# carcomputer.net
KiCad netlist of a schematic drawn in EAGLE
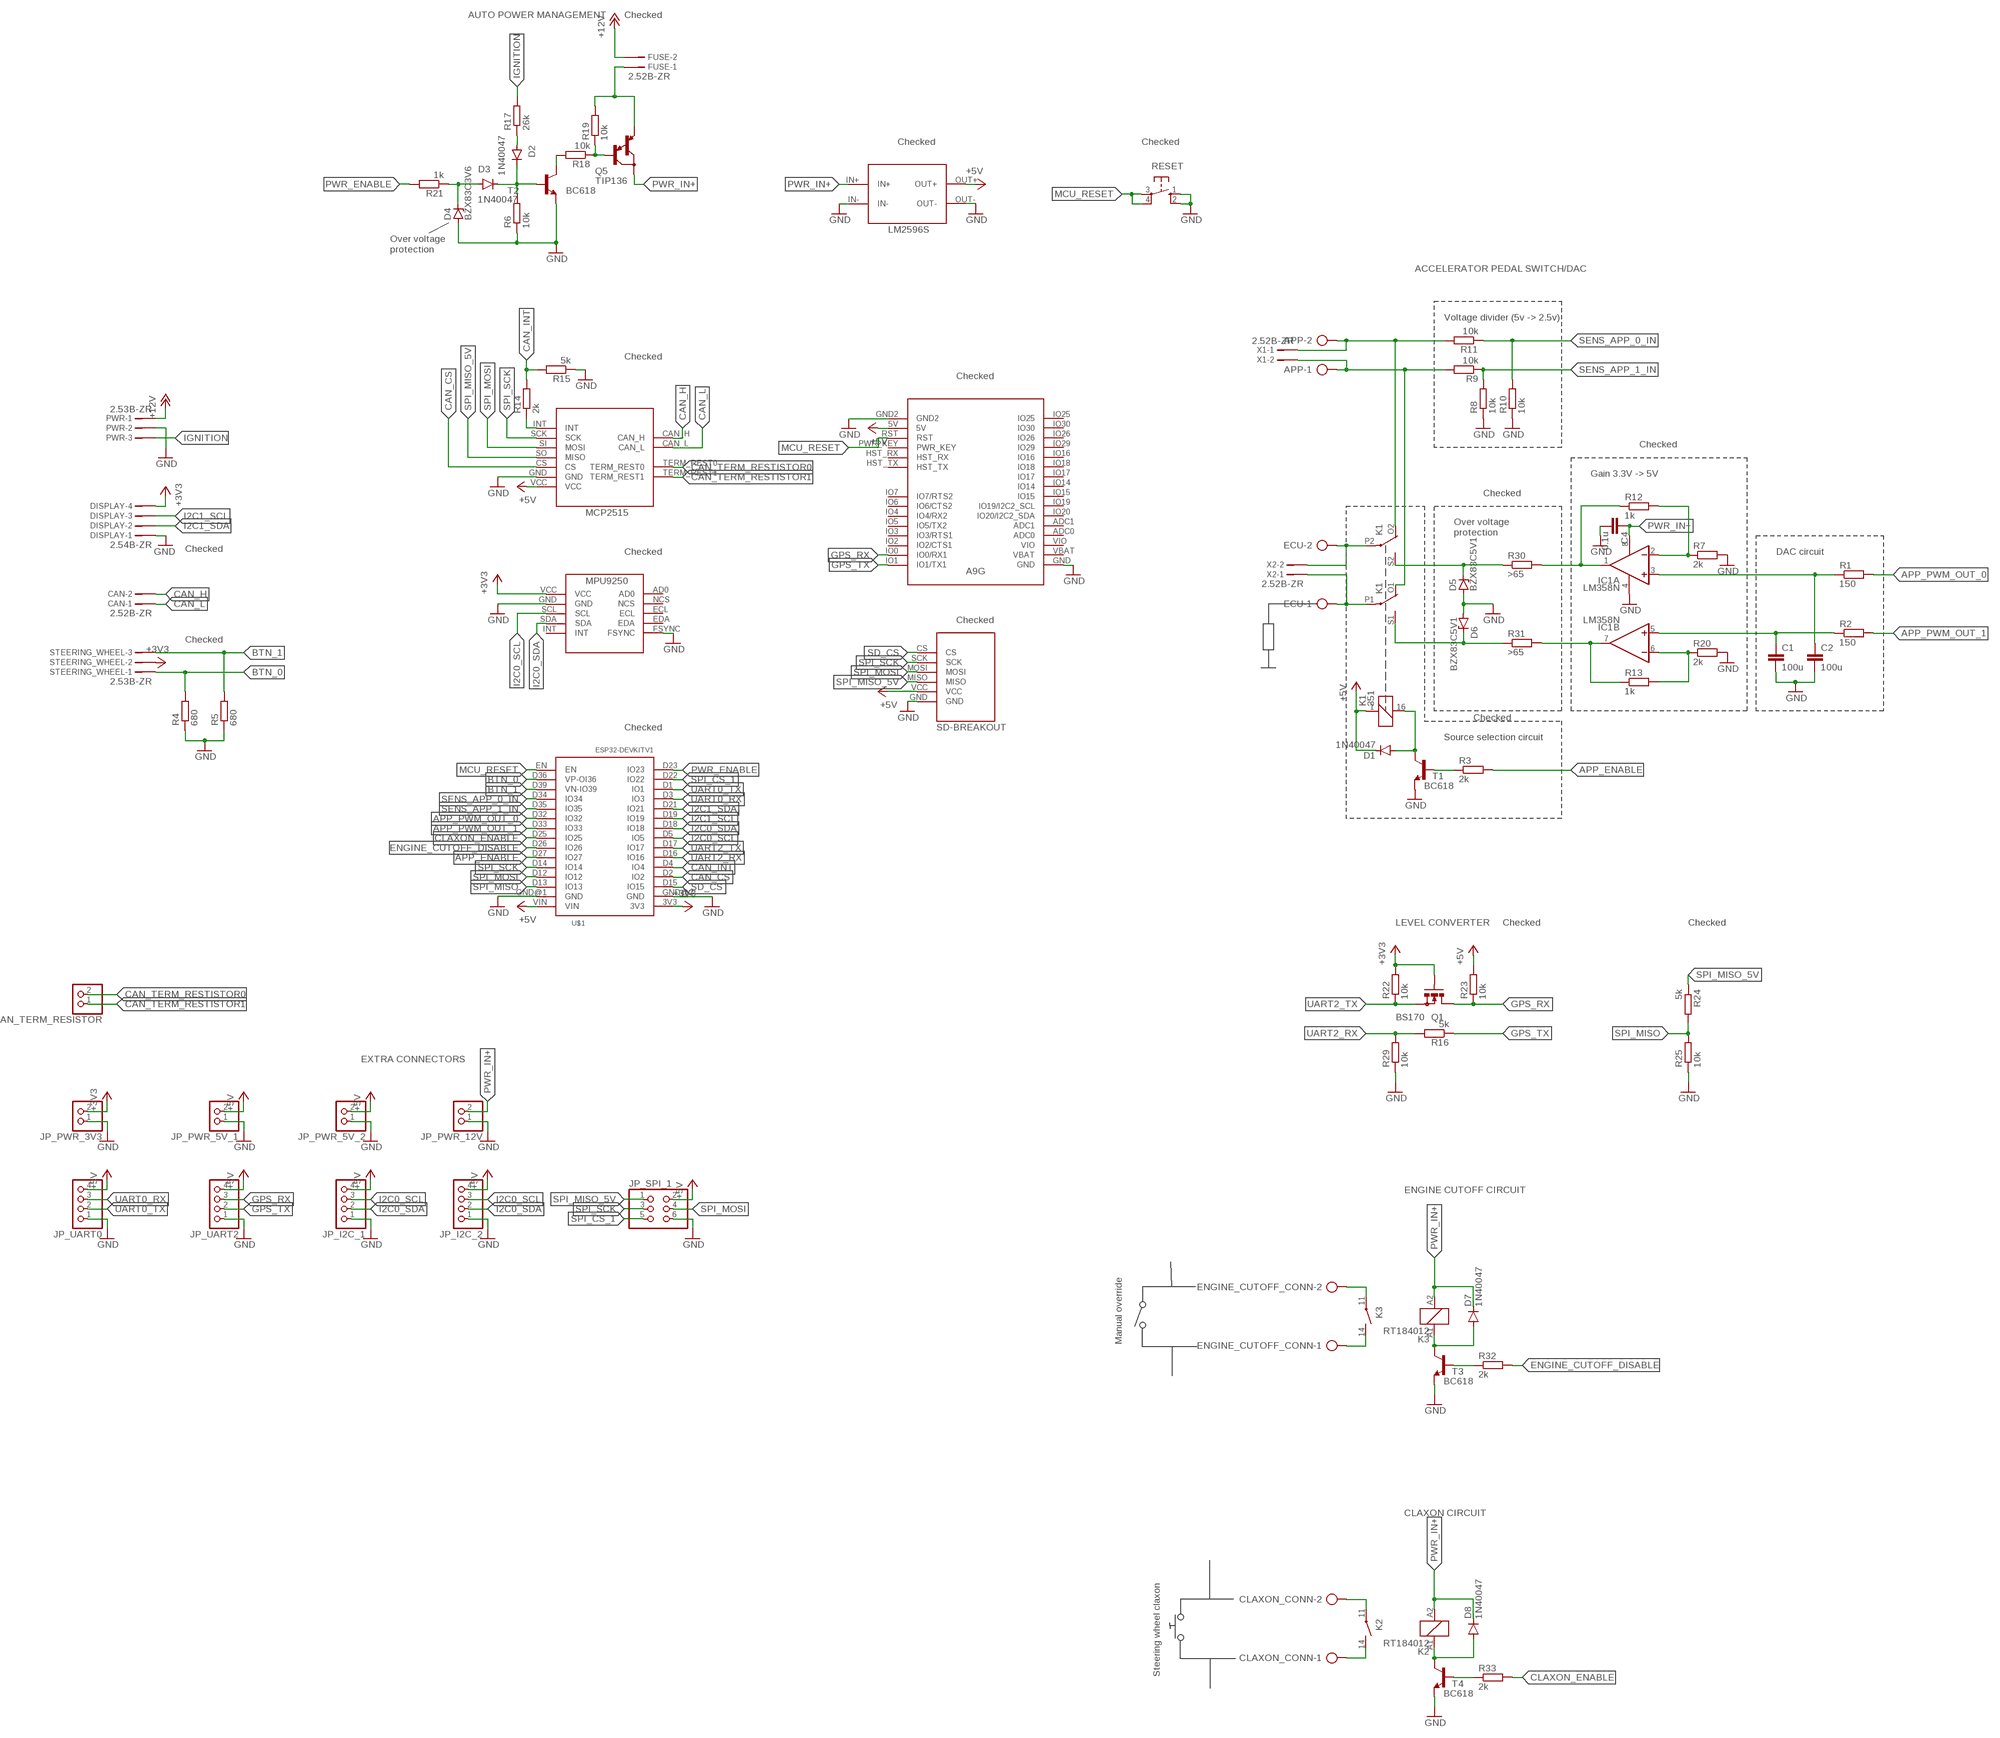
[diagram p0: schematic, sheet 1]

(export (version "E")
  (design (tool "Eeschema 10.0.6"))
  (components
    (comp (ref "APP")
      (value "AK300/2")
      (footprint "eagle-import:AK300_2")
      (libsource (lib "eagle-import") (part "AK300/2"))
    )
    (comp (ref "C1")
      (value "100u")
      (footprint "eagle-import:C025-050X050")
      (libsource (lib "eagle-import") (part "C-EU025-050X050"))
    )
    (comp (ref "C2")
      (value "100u")
      (footprint "eagle-import:C025-050X050")
      (libsource (lib "eagle-import") (part "C-EU025-050X050"))
    )
    (comp (ref "C4")
      (value "0.1u")
      (footprint "eagle-import:C025-050X050")
      (libsource (lib "eagle-import") (part "C-EU025-050X050"))
    )
    (comp (ref "CAN")
      (value "2.52B-ZR")
      (footprint "eagle-import:B2B-ZR2.5")
      (libsource (lib "eagle-import") (part "?2B-ZR2.5"))
    )
    (comp (ref "CAN_TERM_RESISTOR")
      (value "PINHD-1X2")
      (footprint "eagle-import:1X02")
      (libsource (lib "eagle-import") (part "PINHD-1X2"))
    )
    (comp (ref "CLAXON_CONN")
      (value "AK300/2")
      (footprint "eagle-import:AK300_2")
      (libsource (lib "eagle-import") (part "AK300/2"))
    )
    (comp (ref "D1")
      (value "1N40047")
      (footprint "eagle-import:DO41-7.6")
      (libsource (lib "eagle-import") (part "1N40047"))
    )
    (comp (ref "D2")
      (value "1N40047")
      (footprint "eagle-import:DO41-7.6")
      (libsource (lib "eagle-import") (part "1N40047"))
    )
    (comp (ref "D3")
      (value "1N40047")
      (footprint "eagle-import:DO41-7.6")
      (libsource (lib "eagle-import") (part "1N40047"))
    )
    (comp (ref "D4")
      (value "BZX83C3V6")
      (footprint "eagle-import:DO41Z7.6")
      (libsource (lib "eagle-import") (part "BZX857"))
    )
    (comp (ref "D5")
      (value "BZX83C5V1")
      (footprint "eagle-import:DO41Z7.6")
      (libsource (lib "eagle-import") (part "BZX857"))
    )
    (comp (ref "D6")
      (value "BZX83C5V1")
      (footprint "eagle-import:DO41Z7.6")
      (libsource (lib "eagle-import") (part "BZX857"))
    )
    (comp (ref "D7")
      (value "1N40047")
      (footprint "eagle-import:DO41-7.6")
      (libsource (lib "eagle-import") (part "1N40047"))
    )
    (comp (ref "D8")
      (value "1N40047")
      (footprint "eagle-import:DO41-7.6")
      (libsource (lib "eagle-import") (part "1N40047"))
    )
    (comp (ref "DISPLAY")
      (value "2.54B-ZR")
      (footprint "eagle-import:B4B-ZR2.5")
      (libsource (lib "eagle-import") (part "?4B-ZR2.5"))
    )
    (comp (ref "ECU")
      (value "AK300/2")
      (footprint "eagle-import:AK300_2")
      (libsource (lib "eagle-import") (part "AK300/2"))
    )
    (comp (ref "ENGINE_CUTOFF_CONN")
      (value "AK300/2")
      (footprint "eagle-import:AK300_2")
      (libsource (lib "eagle-import") (part "AK300/2"))
    )
    (comp (ref "FUSE")
      (value "2.52B-ZR")
      (footprint "eagle-import:B2B-ZR2.5")
      (libsource (lib "eagle-import") (part "?2B-ZR2.5"))
    )
    (comp (ref "IC1")
      (value "LM358N")
      (footprint "eagle-import:DIL08")
      (libsource (lib "eagle-import") (part "LM358N"))
    )
    (comp (ref "JP_I2C_1")
      (value "PINHD-1X4")
      (footprint "eagle-import:1X04")
      (libsource (lib "eagle-import") (part "PINHD-1X4"))
    )
    (comp (ref "JP_I2C_2")
      (value "PINHD-1X4")
      (footprint "eagle-import:1X04")
      (libsource (lib "eagle-import") (part "PINHD-1X4"))
    )
    (comp (ref "JP_PWR_3V3")
      (value "PINHD-1X2")
      (footprint "eagle-import:1X02")
      (libsource (lib "eagle-import") (part "PINHD-1X2"))
    )
    (comp (ref "JP_PWR_5V_1")
      (value "PINHD-1X2")
      (footprint "eagle-import:1X02")
      (libsource (lib "eagle-import") (part "PINHD-1X2"))
    )
    (comp (ref "JP_PWR_5V_2")
      (value "PINHD-1X2")
      (footprint "eagle-import:1X02")
      (libsource (lib "eagle-import") (part "PINHD-1X2"))
    )
    (comp (ref "JP_PWR_12V")
      (value "PINHD-1X2")
      (footprint "eagle-import:1X02")
      (libsource (lib "eagle-import") (part "PINHD-1X2"))
    )
    (comp (ref "JP_SPI_1")
      (value "PINHD-2X3")
      (footprint "eagle-import:2X03")
      (libsource (lib "eagle-import") (part "PINHD-2X3"))
    )
    (comp (ref "JP_UART0")
      (value "PINHD-1X4")
      (footprint "eagle-import:1X04")
      (libsource (lib "eagle-import") (part "PINHD-1X4"))
    )
    (comp (ref "JP_UART2")
      (value "PINHD-1X4")
      (footprint "eagle-import:1X04")
      (libsource (lib "eagle-import") (part "PINHD-1X4"))
    )
    (comp (ref "K1")
      (value "351")
      (footprint "eagle-import:351")
      (libsource (lib "eagle-import") (part "351"))
    )
    (comp (ref "K2")
      (value "RT184012")
      (footprint "eagle-import:RT-N_O12A3.5")
      (fields (field (name "MF") "TYCO ELECTRONICS"))
      (libsource (lib "eagle-import") (part "RT?184012"))
    )
    (comp (ref "K3")
      (value "RT184012")
      (footprint "eagle-import:RT-N_O12A3.5")
      (fields (field (name "MF") "TYCO ELECTRONICS"))
      (libsource (lib "eagle-import") (part "RT?184012"))
    )
    (comp (ref "PWR")
      (value "2.53B-ZR")
      (footprint "eagle-import:B3B-ZR2.5")
      (libsource (lib "eagle-import") (part "?3B-ZR2.5"))
    )
    (comp (ref "Q1")
      (value "BS170")
      (footprint "eagle-import:SOT54E")
      (libsource (lib "eagle-import") (part "BS170"))
    )
    (comp (ref "Q5")
      (value "TIP136")
      (footprint "eagle-import:TO220")
      (libsource (lib "eagle-import") (part "TIP136"))
    )
    (comp (ref "R1")
      (value "150")
      (footprint "eagle-import:0309_10")
      (libsource (lib "eagle-import") (part "R-EU_0309/10"))
    )
    (comp (ref "R2")
      (value "150")
      (footprint "eagle-import:0309_10")
      (libsource (lib "eagle-import") (part "R-EU_0309/10"))
    )
    (comp (ref "R3")
      (value "2k")
      (footprint "eagle-import:0207_7")
      (libsource (lib "eagle-import") (part "R-EU_0207/7"))
    )
    (comp (ref "R4")
      (value "680")
      (footprint "eagle-import:0207_7")
      (libsource (lib "eagle-import") (part "R-EU_0207/7"))
    )
    (comp (ref "R5")
      (value "680")
      (footprint "eagle-import:0207_7")
      (libsource (lib "eagle-import") (part "R-EU_0207/7"))
    )
    (comp (ref "R6")
      (value "10k")
      (footprint "eagle-import:0207_7")
      (libsource (lib "eagle-import") (part "R-EU_0207/7"))
    )
    (comp (ref "R7")
      (value "2k")
      (footprint "eagle-import:0207_7")
      (libsource (lib "eagle-import") (part "R-EU_0207/7"))
    )
    (comp (ref "R8")
      (value "10k")
      (footprint "eagle-import:0207_7")
      (libsource (lib "eagle-import") (part "R-EU_0207/7"))
    )
    (comp (ref "R9")
      (value "10k")
      (footprint "eagle-import:0309_10")
      (libsource (lib "eagle-import") (part "R-EU_0309/10"))
    )
    (comp (ref "R10")
      (value "10k")
      (footprint "eagle-import:0207_7")
      (libsource (lib "eagle-import") (part "R-EU_0207/7"))
    )
    (comp (ref "R11")
      (value "10k")
      (footprint "eagle-import:0309_10")
      (libsource (lib "eagle-import") (part "R-EU_0309/10"))
    )
    (comp (ref "R12")
      (value "1k")
      (footprint "eagle-import:0207_7")
      (libsource (lib "eagle-import") (part "R-EU_0207/7"))
    )
    (comp (ref "R13")
      (value "1k")
      (footprint "eagle-import:0207_7")
      (libsource (lib "eagle-import") (part "R-EU_0207/7"))
    )
    (comp (ref "R14")
      (value "2k")
      (footprint "eagle-import:0309_10")
      (libsource (lib "eagle-import") (part "R-EU_0309/10"))
    )
    (comp (ref "R15")
      (value "5k")
      (footprint "eagle-import:0207_7")
      (libsource (lib "eagle-import") (part "R-EU_0207/7"))
    )
    (comp (ref "R16")
      (value "5k")
      (footprint "eagle-import:0207_7")
      (libsource (lib "eagle-import") (part "R-EU_0207/7"))
    )
    (comp (ref "R17")
      (value "26k")
      (footprint "eagle-import:0207_7")
      (libsource (lib "eagle-import") (part "R-EU_0207/7"))
    )
    (comp (ref "R18")
      (value "10k")
      (footprint "eagle-import:0207_7")
      (libsource (lib "eagle-import") (part "R-EU_0207/7"))
    )
    (comp (ref "R19")
      (value "10k")
      (footprint "eagle-import:0207_7")
      (libsource (lib "eagle-import") (part "R-EU_0207/7"))
    )
    (comp (ref "R20")
      (value "2k")
      (footprint "eagle-import:0207_7")
      (libsource (lib "eagle-import") (part "R-EU_0207/7"))
    )
    (comp (ref "R21")
      (value "1k")
      (footprint "eagle-import:0309_10")
      (libsource (lib "eagle-import") (part "R-EU_0309/10"))
    )
    (comp (ref "R22")
      (value "10k")
      (footprint "eagle-import:0207_7")
      (libsource (lib "eagle-import") (part "R-EU_0207/7"))
    )
    (comp (ref "R23")
      (value "10k")
      (footprint "eagle-import:0207_7")
      (libsource (lib "eagle-import") (part "R-EU_0207/7"))
    )
    (comp (ref "R24")
      (value "5k")
      (footprint "eagle-import:0207_7")
      (libsource (lib "eagle-import") (part "R-EU_0207/7"))
    )
    (comp (ref "R25")
      (value "10k")
      (footprint "eagle-import:0207_7")
      (libsource (lib "eagle-import") (part "R-EU_0207/7"))
    )
    (comp (ref "R29")
      (value "10k")
      (footprint "eagle-import:0207_7")
      (libsource (lib "eagle-import") (part "R-EU_0207/7"))
    )
    (comp (ref "R30")
      (value ">65")
      (footprint "eagle-import:0207_7")
      (libsource (lib "eagle-import") (part "R-EU_0207/7"))
    )
    (comp (ref "R31")
      (value ">65")
      (footprint "eagle-import:0207_7")
      (libsource (lib "eagle-import") (part "R-EU_0207/7"))
    )
    (comp (ref "R32")
      (value "2k")
      (footprint "eagle-import:0309_10")
      (libsource (lib "eagle-import") (part "R-EU_0309/10"))
    )
    (comp (ref "R33")
      (value "2k")
      (footprint "eagle-import:0309_10")
      (libsource (lib "eagle-import") (part "R-EU_0309/10"))
    )
    (comp (ref "RESET")
      (value "10-XX")
      (footprint "eagle-import:B3F-10XX")
      (fields (field (name "MPN") "B3F-1000"))
      (libsource (lib "eagle-import") (part "10-XX"))
    )
    (comp (ref "STEERING_WHEEL")
      (value "2.53B-ZR")
      (footprint "eagle-import:B3B-ZR2.5")
      (libsource (lib "eagle-import") (part "?3B-ZR2.5"))
    )
    (comp (ref "T1")
      (value "BC618")
      (footprint "eagle-import:TO92-EBC")
      (libsource (lib "eagle-import") (part "BC618"))
    )
    (comp (ref "T2")
      (value "BC618")
      (footprint "eagle-import:TO92-EBC")
      (libsource (lib "eagle-import") (part "BC618"))
    )
    (comp (ref "T3")
      (value "BC618")
      (footprint "eagle-import:TO92-EBC")
      (libsource (lib "eagle-import") (part "BC618"))
    )
    (comp (ref "T4")
      (value "BC618")
      (footprint "eagle-import:TO92-EBC")
      (libsource (lib "eagle-import") (part "BC618"))
    )
    (comp (ref "U$1")
      (value "ESP32DEVKITV1")
      (footprint "eagle-import:ESP32-DEVKITV1")
      (libsource (lib "eagle-import") (part "ESP32DEVKITV1"))
    )
    (comp (ref "U$2")
      (value "MCP2515_DEVBOARDINVERTED")
      (footprint "eagle-import:MCP2515_DEVBOARD_INVERTED")
      (libsource (lib "eagle-import") (part "MCP2515_DEVBOARDINVERTED"))
    )
    (comp (ref "U$3")
      (value "MPU9250_BREAKOUT")
      (footprint "eagle-import:MPU9250_BREAKOUT")
      (libsource (lib "eagle-import") (part "MPU9250_BREAKOUT"))
    )
    (comp (ref "U$4")
      (value "LM2596S")
      (footprint "eagle-import:LM2596S")
      (libsource (lib "eagle-import") (part "LM2596S"))
    )
    (comp (ref "U$5")
      (value "HKD-MICRO-SD-BREAKOUTH")
      (footprint "eagle-import:HKD-MICRO-SD-BREAKOUT")
      (libsource (lib "eagle-import") (part "HKD-MICRO-SD-BREAKOUTH"))
    )
    (comp (ref "U$6")
      (value "A9G")
      (footprint "eagle-import:A9G")
      (libsource (lib "eagle-import") (part "A9G"))
    )
    (comp (ref "X1")
      (value "2.52B-ZR")
      (footprint "eagle-import:B2B-ZR2.5")
      (libsource (lib "eagle-import") (part "?2B-ZR2.5"))
    )
    (comp (ref "X2")
      (value "2.52B-ZR")
      (footprint "eagle-import:B2B-ZR2.5")
      (libsource (lib "eagle-import") (part "?2B-ZR2.5"))
    )
  )
  (nets
    (net (code "1") (name "+3V3") (class "Default")
      (node (ref "DISPLAY") (pin "4") (pinfunction "1_4") (pintype "passive"))
      (node (ref "JP_PWR_3V3") (pin "2") (pinfunction "2_2") (pintype "passive"))
      (node (ref "Q1") (pin "G") (pinfunction "G_G") (pintype "passive"))
      (node (ref "R22") (pin "2") (pinfunction "2_2") (pintype "passive"))
      (node (ref "STEERING_WHEEL") (pin "2") (pinfunction "1_2") (pintype "passive"))
      (node (ref "U$1") (pin "3V3") (pinfunction "3V3_3V3") (pintype "bidirectional"))
      (node (ref "U$3") (pin "VCC") (pinfunction "VCC_VCC") (pintype "bidirectional"))
    )
    (net (code "2") (name "+5V") (class "Default")
      (node (ref "D1") (pin "C") (pinfunction "C_C") (pintype "passive"))
      (node (ref "JP_I2C_1") (pin "4") (pinfunction "4_4") (pintype "passive"))
      (node (ref "JP_I2C_2") (pin "4") (pinfunction "4_4") (pintype "passive"))
      (node (ref "JP_PWR_5V_1") (pin "2") (pinfunction "2_2") (pintype "passive"))
      (node (ref "JP_PWR_5V_2") (pin "2") (pinfunction "2_2") (pintype "passive"))
      (node (ref "JP_SPI_1") (pin "2") (pinfunction "2_2") (pintype "passive"))
      (node (ref "JP_UART0") (pin "4") (pinfunction "4_4") (pintype "passive"))
      (node (ref "JP_UART2") (pin "4") (pinfunction "4_4") (pintype "passive"))
      (node (ref "K1") (pin "1") (pinfunction "1_1") (pintype "passive"))
      (node (ref "R23") (pin "2") (pinfunction "2_2") (pintype "passive"))
      (node (ref "U$1") (pin "VIN") (pinfunction "VIN_VIN") (pintype "bidirectional"))
      (node (ref "U$2") (pin "VCC") (pinfunction "VCC_VCC") (pintype "bidirectional"))
      (node (ref "U$4") (pin "OUT+") (pinfunction "OUT+_OUT+") (pintype "bidirectional"))
      (node (ref "U$5") (pin "VCC") (pinfunction "VCC_VCC") (pintype "bidirectional"))
      (node (ref "U$6") (pin "5V") (pinfunction "5V_5V") (pintype "bidirectional"))
    )
    (net (code "3") (name "+12V") (class "Default")
      (node (ref "FUSE") (pin "2") (pinfunction "1_2") (pintype "passive"))
      (node (ref "PWR") (pin "1") (pinfunction "1_1") (pintype "passive"))
    )
    (net (code "4") (name "APP_ENABLE") (class "Default")
      (node (ref "R3") (pin "2") (pinfunction "2_2") (pintype "passive"))
      (node (ref "U$1") (pin "D27") (pinfunction "IO27_D27") (pintype "bidirectional"))
    )
    (net (code "5") (name "APP_PWM_OUT_0") (class "Default")
      (node (ref "R1") (pin "2") (pinfunction "2_2") (pintype "passive"))
      (node (ref "U$1") (pin "D32") (pinfunction "IO32_D32") (pintype "bidirectional"))
    )
    (net (code "6") (name "APP_PWM_OUT_1") (class "Default")
      (node (ref "R2") (pin "2") (pinfunction "2_2") (pintype "passive"))
      (node (ref "U$1") (pin "D33") (pinfunction "IO33_D33") (pintype "bidirectional"))
    )
    (net (code "7") (name "BTN_0") (class "Default")
      (node (ref "R4") (pin "2") (pinfunction "2_2") (pintype "passive"))
      (node (ref "STEERING_WHEEL") (pin "1") (pinfunction "1_1") (pintype "passive"))
      (node (ref "U$1") (pin "D36") (pinfunction "VP-OI36_D36") (pintype "bidirectional"))
    )
    (net (code "8") (name "BTN_1") (class "Default")
      (node (ref "R5") (pin "2") (pinfunction "2_2") (pintype "passive"))
      (node (ref "STEERING_WHEEL") (pin "3") (pinfunction "1_3") (pintype "passive"))
      (node (ref "U$1") (pin "D39") (pinfunction "VN-IO39_D39") (pintype "bidirectional"))
    )
    (net (code "9") (name "CAN_CS") (class "Default")
      (node (ref "U$1") (pin "D2") (pinfunction "IO2_D2") (pintype "bidirectional"))
      (node (ref "U$2") (pin "CS") (pinfunction "CS_CS") (pintype "input"))
    )
    (net (code "10") (name "CAN_H") (class "Default")
      (node (ref "CAN") (pin "2") (pinfunction "1_2") (pintype "passive"))
      (node (ref "U$2") (pin "CAN_H") (pinfunction "CAN_H_CAN_H") (pintype "bidirectional"))
    )
    (net (code "11") (name "CAN_INT") (class "Default")
      (node (ref "R14") (pin "2") (pinfunction "2_2") (pintype "passive"))
      (node (ref "R15") (pin "2") (pinfunction "2_2") (pintype "passive"))
      (node (ref "U$1") (pin "D4") (pinfunction "IO4_D4") (pintype "bidirectional"))
    )
    (net (code "12") (name "CAN_L") (class "Default")
      (node (ref "CAN") (pin "1") (pinfunction "1_1") (pintype "passive"))
      (node (ref "U$2") (pin "CAN_L") (pinfunction "CAN_L_CAN_L") (pintype "bidirectional"))
    )
    (net (code "13") (name "CAN_TERM_RESTISTOR0") (class "Default")
      (node (ref "CAN_TERM_RESISTOR") (pin "2") (pinfunction "2_2") (pintype "passive"))
      (node (ref "U$2") (pin "TERM_REST0") (pinfunction "TERM_REST0_TERM_REST0") (pintype "bidirectional"))
    )
    (net (code "14") (name "CAN_TERM_RESTISTOR1") (class "Default")
      (node (ref "CAN_TERM_RESISTOR") (pin "1") (pinfunction "1_1") (pintype "passive"))
      (node (ref "U$2") (pin "TERM_REST1") (pinfunction "TERM_REST1_TERM_REST1") (pintype "bidirectional"))
    )
    (net (code "15") (name "CLAXON_ENABLE") (class "Default")
      (node (ref "R33") (pin "2") (pinfunction "2_2") (pintype "passive"))
      (node (ref "U$1") (pin "D25") (pinfunction "IO25_D25") (pintype "bidirectional"))
    )
    (net (code "16") (name "ENGINE_CUTOFF_DISABLE") (class "Default")
      (node (ref "R32") (pin "2") (pinfunction "2_2") (pintype "passive"))
      (node (ref "U$1") (pin "D26") (pinfunction "IO26_D26") (pintype "bidirectional"))
    )
    (net (code "17") (name "GND") (class "Default")
      (node (ref "C1") (pin "2") (pinfunction "2_2") (pintype "passive"))
      (node (ref "C2") (pin "2") (pinfunction "2_2") (pintype "passive"))
      (node (ref "C4") (pin "2") (pinfunction "2_2") (pintype "passive"))
      (node (ref "D4") (pin "A") (pinfunction "A_A") (pintype "passive"))
      (node (ref "D5") (pin "A") (pinfunction "A_A") (pintype "passive"))
      (node (ref "D6") (pin "A") (pinfunction "A_A") (pintype "passive"))
      (node (ref "DISPLAY") (pin "1") (pinfunction "1_1") (pintype "passive"))
      (node (ref "IC1") (pin "4") (pinfunction "V-_4") (pintype "power_in"))
      (node (ref "JP_I2C_1") (pin "1") (pinfunction "1_1") (pintype "passive"))
      (node (ref "JP_I2C_2") (pin "1") (pinfunction "1_1") (pintype "passive"))
      (node (ref "JP_PWR_12V") (pin "1") (pinfunction "1_1") (pintype "passive"))
      (node (ref "JP_PWR_3V3") (pin "1") (pinfunction "1_1") (pintype "passive"))
      (node (ref "JP_PWR_5V_1") (pin "1") (pinfunction "1_1") (pintype "passive"))
      (node (ref "JP_PWR_5V_2") (pin "1") (pinfunction "1_1") (pintype "passive"))
      (node (ref "JP_SPI_1") (pin "6") (pinfunction "6_6") (pintype "passive"))
      (node (ref "JP_UART0") (pin "1") (pinfunction "1_1") (pintype "passive"))
      (node (ref "JP_UART2") (pin "1") (pinfunction "1_1") (pintype "passive"))
      (node (ref "PWR") (pin "2") (pinfunction "1_2") (pintype "passive"))
      (node (ref "R10") (pin "1") (pinfunction "1_1") (pintype "passive"))
      (node (ref "R15") (pin "1") (pinfunction "1_1") (pintype "passive"))
      (node (ref "R20") (pin "2") (pinfunction "2_2") (pintype "passive"))
      (node (ref "R25") (pin "1") (pinfunction "1_1") (pintype "passive"))
      (node (ref "R29") (pin "1") (pinfunction "1_1") (pintype "passive"))
      (node (ref "R4") (pin "1") (pinfunction "1_1") (pintype "passive"))
      (node (ref "R5") (pin "1") (pinfunction "1_1") (pintype "passive"))
      (node (ref "R6") (pin "1") (pinfunction "1_1") (pintype "passive"))
      (node (ref "R7") (pin "2") (pinfunction "2_2") (pintype "passive"))
      (node (ref "R8") (pin "1") (pinfunction "1_1") (pintype "passive"))
      (node (ref "RESET") (pin "1") (pinfunction "S_1") (pintype "passive"))
      (node (ref "RESET") (pin "2") (pinfunction "S1_2") (pintype "passive"))
      (node (ref "T1") (pin "E") (pinfunction "E_E") (pintype "passive"))
      (node (ref "T2") (pin "E") (pinfunction "E_E") (pintype "passive"))
      (node (ref "T3") (pin "E") (pinfunction "E_E") (pintype "passive"))
      (node (ref "T4") (pin "E") (pinfunction "E_E") (pintype "passive"))
      (node (ref "U$1") (pin "GND@1") (pinfunction "GND_GND@1") (pintype "bidirectional"))
      (node (ref "U$1") (pin "GND@2") (pinfunction "GND_GND@2") (pintype "bidirectional"))
      (node (ref "U$2") (pin "GND") (pinfunction "GND_GND") (pintype "bidirectional"))
      (node (ref "U$3") (pin "FSYNC") (pinfunction "FSYNC_FSYNC") (pintype "bidirectional"))
      (node (ref "U$3") (pin "GND") (pinfunction "GND_GND") (pintype "bidirectional"))
      (node (ref "U$4") (pin "IN-") (pinfunction "IN-_IN-") (pintype "bidirectional"))
      (node (ref "U$4") (pin "OUT-") (pinfunction "OUT-_OUT-") (pintype "bidirectional"))
      (node (ref "U$5") (pin "GND") (pinfunction "GND_GND") (pintype "bidirectional"))
      (node (ref "U$6") (pin "GND") (pinfunction "GND_GND") (pintype "bidirectional"))
      (node (ref "U$6") (pin "GND2") (pinfunction "GND2_GND2") (pintype "bidirectional"))
    )
    (net (code "18") (name "GPS_RX") (class "Default")
      (node (ref "JP_UART2") (pin "3") (pinfunction "3_3") (pintype "passive"))
      (node (ref "Q1") (pin "D") (pinfunction "D_D") (pintype "passive"))
      (node (ref "R23") (pin "1") (pinfunction "1_1") (pintype "passive"))
      (node (ref "U$6") (pin "IO0") (pinfunction "IO0/RX1_IO0") (pintype "bidirectional"))
    )
    (net (code "19") (name "GPS_TX") (class "Default")
      (node (ref "JP_UART2") (pin "2") (pinfunction "2_2") (pintype "passive"))
      (node (ref "R16") (pin "1") (pinfunction "1_1") (pintype "passive"))
      (node (ref "U$6") (pin "IO1") (pinfunction "IO1/TX1_IO1") (pintype "bidirectional"))
    )
    (net (code "20") (name "I2C0_SCL") (class "Default")
      (node (ref "JP_I2C_1") (pin "3") (pinfunction "3_3") (pintype "passive"))
      (node (ref "JP_I2C_2") (pin "3") (pinfunction "3_3") (pintype "passive"))
      (node (ref "U$1") (pin "D5") (pinfunction "IO5_D5") (pintype "bidirectional"))
      (node (ref "U$3") (pin "SCL") (pinfunction "SCL_SCL") (pintype "bidirectional"))
    )
    (net (code "21") (name "I2C0_SDA") (class "Default")
      (node (ref "JP_I2C_1") (pin "2") (pinfunction "2_2") (pintype "passive"))
      (node (ref "JP_I2C_2") (pin "2") (pinfunction "2_2") (pintype "passive"))
      (node (ref "U$1") (pin "D18") (pinfunction "IO18_D18") (pintype "bidirectional"))
      (node (ref "U$3") (pin "SDA") (pinfunction "SDA_SDA") (pintype "bidirectional"))
    )
    (net (code "22") (name "I2C1_SCL") (class "Default")
      (node (ref "DISPLAY") (pin "3") (pinfunction "1_3") (pintype "passive"))
      (node (ref "U$1") (pin "D19") (pinfunction "IO19_D19") (pintype "bidirectional"))
    )
    (net (code "23") (name "I2C1_SDA") (class "Default")
      (node (ref "DISPLAY") (pin "2") (pinfunction "1_2") (pintype "passive"))
      (node (ref "U$1") (pin "D21") (pinfunction "IO21_D21") (pintype "bidirectional"))
    )
    (net (code "24") (name "IGNITION") (class "Default")
      (node (ref "PWR") (pin "3") (pinfunction "1_3") (pintype "passive"))
      (node (ref "R17") (pin "2") (pinfunction "2_2") (pintype "passive"))
    )
    (net (code "25") (name "MCU_RESET") (class "Default")
      (node (ref "RESET") (pin "3") (pinfunction "P_3") (pintype "passive"))
      (node (ref "RESET") (pin "4") (pinfunction "P1_4") (pintype "passive"))
      (node (ref "U$1") (pin "EN") (pinfunction "EN_EN") (pintype "bidirectional"))
      (node (ref "U$6") (pin "RST") (pinfunction "RST_RST") (pintype "bidirectional"))
    )
    (net (code "26") (name "Net-(APPA-KL)") (class "Default")
      (node (ref "APP") (pin "1") (pinfunction "KL_1") (pintype "passive"))
      (node (ref "K1") (pin "O1") (pinfunction "O_O1") (pintype "passive"))
      (node (ref "R9") (pin "2") (pinfunction "2_2") (pintype "passive"))
      (node (ref "X1") (pin "2") (pinfunction "1_2") (pintype "passive"))
    )
    (net (code "27") (name "Net-(APPB-KL)") (class "Default")
      (node (ref "APP") (pin "2") (pinfunction "KL_2") (pintype "passive"))
      (node (ref "K1") (pin "O2") (pinfunction "O_O2") (pintype "passive"))
      (node (ref "R11") (pin "2") (pinfunction "2_2") (pintype "passive"))
      (node (ref "X1") (pin "1") (pinfunction "1_1") (pintype "passive"))
    )
    (net (code "28") (name "Net-(CLAXON_CONNA-KL)") (class "Default")
      (node (ref "CLAXON_CONN") (pin "1") (pinfunction "KL_1") (pintype "passive"))
      (node (ref "K2") (pin "14") (pinfunction "S_14") (pintype "passive"))
    )
    (net (code "29") (name "Net-(CLAXON_CONNB-KL)") (class "Default")
      (node (ref "CLAXON_CONN") (pin "2") (pinfunction "KL_2") (pintype "passive"))
      (node (ref "K2") (pin "11") (pinfunction "P_11") (pintype "passive"))
    )
    (net (code "30") (name "Net-(D2-PadA)") (class "Default")
      (node (ref "D2") (pin "A") (pinfunction "A_A") (pintype "passive"))
      (node (ref "R17") (pin "1") (pinfunction "1_1") (pintype "passive"))
    )
    (net (code "31") (name "Net-(D2-PadC)") (class "Default")
      (node (ref "D2") (pin "C") (pinfunction "C_C") (pintype "passive"))
      (node (ref "D3") (pin "C") (pinfunction "C_C") (pintype "passive"))
      (node (ref "R6") (pin "2") (pinfunction "2_2") (pintype "passive"))
      (node (ref "T2") (pin "B") (pinfunction "B_B") (pintype "passive"))
    )
    (net (code "32") (name "Net-(D3-PadA)") (class "Default")
      (node (ref "D3") (pin "A") (pinfunction "A_A") (pintype "passive"))
      (node (ref "D4") (pin "C") (pinfunction "C_C") (pintype "passive"))
      (node (ref "R21") (pin "1") (pinfunction "1_1") (pintype "passive"))
    )
    (net (code "33") (name "Net-(ECUA-KL)") (class "Default")
      (node (ref "ECU") (pin "1") (pinfunction "KL_1") (pintype "passive"))
      (node (ref "K1") (pin "P1") (pinfunction "P_P1") (pintype "passive"))
      (node (ref "X2") (pin "1") (pinfunction "1_1") (pintype "passive"))
    )
    (net (code "34") (name "Net-(ECUB-KL)") (class "Default")
      (node (ref "ECU") (pin "2") (pinfunction "KL_2") (pintype "passive"))
      (node (ref "K1") (pin "P2") (pinfunction "P_P2") (pintype "passive"))
      (node (ref "X2") (pin "2") (pinfunction "1_2") (pintype "passive"))
    )
    (net (code "35") (name "Net-(ENGINE_CUTOFF_CONNA-KL)") (class "Default")
      (node (ref "ENGINE_CUTOFF_CONN") (pin "1") (pinfunction "KL_1") (pintype "passive"))
      (node (ref "K3") (pin "14") (pinfunction "S_14") (pintype "passive"))
    )
    (net (code "36") (name "Net-(ENGINE_CUTOFF_CONNB-KL)") (class "Default")
      (node (ref "ENGINE_CUTOFF_CONN") (pin "2") (pinfunction "KL_2") (pintype "passive"))
      (node (ref "K3") (pin "11") (pinfunction "P_11") (pintype "passive"))
    )
    (net (code "37") (name "Net-(IC1A-+IN)") (class "Default")
      (node (ref "C2") (pin "1") (pinfunction "1_1") (pintype "passive"))
      (node (ref "IC1") (pin "3") (pinfunction "+IN_3") (pintype "input"))
      (node (ref "R1") (pin "1") (pinfunction "1_1") (pintype "passive"))
    )
    (net (code "38") (name "Net-(IC1A--IN)") (class "Default")
      (node (ref "IC1") (pin "2") (pinfunction "-IN_2") (pintype "input"))
      (node (ref "R12") (pin "2") (pinfunction "2_2") (pintype "passive"))
      (node (ref "R7") (pin "1") (pinfunction "1_1") (pintype "passive"))
    )
    (net (code "39") (name "Net-(IC1A-OUT)") (class "Default")
      (node (ref "IC1") (pin "1") (pinfunction "OUT_1") (pintype "output"))
      (node (ref "R12") (pin "1") (pinfunction "1_1") (pintype "passive"))
      (node (ref "R30") (pin "2") (pinfunction "2_2") (pintype "passive"))
    )
    (net (code "40") (name "Net-(IC1B-+IN)") (class "Default")
      (node (ref "C1") (pin "1") (pinfunction "1_1") (pintype "passive"))
      (node (ref "IC1") (pin "5") (pinfunction "+IN_5") (pintype "input"))
      (node (ref "R2") (pin "1") (pinfunction "1_1") (pintype "passive"))
    )
    (net (code "41") (name "Net-(IC1B--IN)") (class "Default")
      (node (ref "IC1") (pin "6") (pinfunction "-IN_6") (pintype "input"))
      (node (ref "R13") (pin "2") (pinfunction "2_2") (pintype "passive"))
      (node (ref "R20") (pin "1") (pinfunction "1_1") (pintype "passive"))
    )
    (net (code "42") (name "Net-(IC1B-OUT)") (class "Default")
      (node (ref "IC1") (pin "7") (pinfunction "OUT_7") (pintype "output"))
      (node (ref "R13") (pin "1") (pinfunction "1_1") (pintype "passive"))
      (node (ref "R31") (pin "2") (pinfunction "2_2") (pintype "passive"))
    )
    (net (code "43") (name "Net-(K1A-2)") (class "Default")
      (node (ref "D1") (pin "A") (pinfunction "A_A") (pintype "passive"))
      (node (ref "K1") (pin "16") (pinfunction "2_16") (pintype "passive"))
      (node (ref "T1") (pin "C") (pinfunction "C_C") (pintype "passive"))
    )
    (net (code "44") (name "Net-(K1B-S)") (class "Default")
      (node (ref "D6") (pin "C") (pinfunction "C_C") (pintype "passive"))
      (node (ref "K1") (pin "S1") (pinfunction "S_S1") (pintype "passive"))
      (node (ref "R31") (pin "1") (pinfunction "1_1") (pintype "passive"))
    )
    (net (code "45") (name "Net-(K1C-S)") (class "Default")
      (node (ref "D5") (pin "C") (pinfunction "C_C") (pintype "passive"))
      (node (ref "K1") (pin "S2") (pinfunction "S_S2") (pintype "passive"))
      (node (ref "R30") (pin "1") (pinfunction "1_1") (pintype "passive"))
    )
    (net (code "46") (name "Net-(K2A-1)") (class "Default")
      (node (ref "D8") (pin "A") (pinfunction "A_A") (pintype "passive"))
      (node (ref "K2") (pin "A1") (pinfunction "1_A1") (pintype "passive"))
      (node (ref "T4") (pin "C") (pinfunction "C_C") (pintype "passive"))
    )
    (net (code "47") (name "Net-(K3A-1)") (class "Default")
      (node (ref "D7") (pin "A") (pinfunction "A_A") (pintype "passive"))
      (node (ref "K3") (pin "A1") (pinfunction "1_A1") (pintype "passive"))
      (node (ref "T3") (pin "C") (pinfunction "C_C") (pintype "passive"))
    )
    (net (code "48") (name "Net-(Q5-B)") (class "Default")
      (node (ref "Q5") (pin "1") (pinfunction "B_1") (pintype "passive"))
      (node (ref "R18") (pin "1") (pinfunction "1_1") (pintype "passive"))
      (node (ref "R19") (pin "1") (pinfunction "1_1") (pintype "passive"))
    )
    (net (code "49") (name "Net-(Q5-E)") (class "Default")
      (node (ref "FUSE") (pin "1") (pinfunction "1_1") (pintype "passive"))
      (node (ref "Q5") (pin "3") (pinfunction "E_3") (pintype "passive"))
      (node (ref "R19") (pin "2") (pinfunction "2_2") (pintype "passive"))
    )
    (net (code "50") (name "Net-(R3-Pad1)") (class "Default")
      (node (ref "R3") (pin "1") (pinfunction "1_1") (pintype "passive"))
      (node (ref "T1") (pin "B") (pinfunction "B_B") (pintype "passive"))
    )
    (net (code "51") (name "Net-(R14-Pad1)") (class "Default")
      (node (ref "R14") (pin "1") (pinfunction "1_1") (pintype "passive"))
      (node (ref "U$2") (pin "INT") (pinfunction "INT_INT") (pintype "output"))
    )
    (net (code "52") (name "Net-(R18-Pad2)") (class "Default")
      (node (ref "R18") (pin "2") (pinfunction "2_2") (pintype "passive"))
      (node (ref "T2") (pin "C") (pinfunction "C_C") (pintype "passive"))
    )
    (net (code "53") (name "Net-(R32-Pad1)") (class "Default")
      (node (ref "R32") (pin "1") (pinfunction "1_1") (pintype "passive"))
      (node (ref "T3") (pin "B") (pinfunction "B_B") (pintype "passive"))
    )
    (net (code "54") (name "Net-(R33-Pad1)") (class "Default")
      (node (ref "R33") (pin "1") (pinfunction "1_1") (pintype "passive"))
      (node (ref "T4") (pin "B") (pinfunction "B_B") (pintype "passive"))
    )
    (net (code "55") (name "PWR_ENABLE") (class "Default")
      (node (ref "R21") (pin "2") (pinfunction "2_2") (pintype "passive"))
      (node (ref "U$1") (pin "D23") (pinfunction "IO23_D23") (pintype "bidirectional"))
    )
    (net (code "56") (name "PWR_IN+") (class "Default")
      (node (ref "C4") (pin "1") (pinfunction "1_1") (pintype "passive"))
      (node (ref "D7") (pin "C") (pinfunction "C_C") (pintype "passive"))
      (node (ref "D8") (pin "C") (pinfunction "C_C") (pintype "passive"))
      (node (ref "IC1") (pin "8") (pinfunction "V+_8") (pintype "power_in"))
      (node (ref "JP_PWR_12V") (pin "2") (pinfunction "2_2") (pintype "passive"))
      (node (ref "K2") (pin "A2") (pinfunction "2_A2") (pintype "passive"))
      (node (ref "K3") (pin "A2") (pinfunction "2_A2") (pintype "passive"))
      (node (ref "Q5") (pin "2") (pinfunction "C_2") (pintype "passive"))
      (node (ref "U$4") (pin "IN+") (pinfunction "IN+_IN+") (pintype "bidirectional"))
    )
    (net (code "57") (name "SD_CS") (class "Default")
      (node (ref "U$1") (pin "D15") (pinfunction "IO15_D15") (pintype "bidirectional"))
      (node (ref "U$5") (pin "CS") (pinfunction "CS_CS") (pintype "bidirectional"))
    )
    (net (code "58") (name "SENS_APP_0_IN") (class "Default")
      (node (ref "R10") (pin "2") (pinfunction "2_2") (pintype "passive"))
      (node (ref "R11") (pin "1") (pinfunction "1_1") (pintype "passive"))
      (node (ref "U$1") (pin "D34") (pinfunction "IO34_D34") (pintype "bidirectional"))
    )
    (net (code "59") (name "SENS_APP_1_IN") (class "Default")
      (node (ref "R8") (pin "2") (pinfunction "2_2") (pintype "passive"))
      (node (ref "R9") (pin "1") (pinfunction "1_1") (pintype "passive"))
      (node (ref "U$1") (pin "D35") (pinfunction "IO35_D35") (pintype "bidirectional"))
    )
    (net (code "60") (name "SPI_CS_1") (class "Default")
      (node (ref "JP_SPI_1") (pin "5") (pinfunction "5_5") (pintype "passive"))
      (node (ref "U$1") (pin "D22") (pinfunction "IO22_D22") (pintype "bidirectional"))
    )
    (net (code "61") (name "SPI_MISO") (class "Default")
      (node (ref "R24") (pin "2") (pinfunction "2_2") (pintype "passive"))
      (node (ref "R25") (pin "2") (pinfunction "2_2") (pintype "passive"))
      (node (ref "U$1") (pin "D13") (pinfunction "IO13_D13") (pintype "bidirectional"))
    )
    (net (code "62") (name "SPI_MISO_5V") (class "Default")
      (node (ref "JP_SPI_1") (pin "1") (pinfunction "1_1") (pintype "passive"))
      (node (ref "R24") (pin "1") (pinfunction "1_1") (pintype "passive"))
      (node (ref "U$2") (pin "SO") (pinfunction "MISO_SO") (pintype "output"))
      (node (ref "U$5") (pin "MISO") (pinfunction "MISO_MISO") (pintype "bidirectional"))
    )
    (net (code "63") (name "SPI_MOSI") (class "Default")
      (node (ref "JP_SPI_1") (pin "4") (pinfunction "4_4") (pintype "passive"))
      (node (ref "U$1") (pin "D12") (pinfunction "IO12_D12") (pintype "bidirectional"))
      (node (ref "U$2") (pin "SI") (pinfunction "MOSI_SI") (pintype "input"))
      (node (ref "U$5") (pin "MOSI") (pinfunction "MOSI_MOSI") (pintype "bidirectional"))
    )
    (net (code "64") (name "SPI_SCK") (class "Default")
      (node (ref "JP_SPI_1") (pin "3") (pinfunction "3_3") (pintype "passive"))
      (node (ref "U$1") (pin "D14") (pinfunction "IO14_D14") (pintype "bidirectional"))
      (node (ref "U$2") (pin "SCK") (pinfunction "SCK_SCK") (pintype "input"))
      (node (ref "U$5") (pin "SCK") (pinfunction "SCK_SCK") (pintype "bidirectional"))
    )
    (net (code "65") (name "UART0_RX") (class "Default")
      (node (ref "JP_UART0") (pin "3") (pinfunction "3_3") (pintype "passive"))
      (node (ref "U$1") (pin "D3") (pinfunction "IO3_D3") (pintype "bidirectional"))
    )
    (net (code "66") (name "UART0_TX") (class "Default")
      (node (ref "JP_UART0") (pin "2") (pinfunction "2_2") (pintype "passive"))
      (node (ref "U$1") (pin "D1") (pinfunction "IO1_D1") (pintype "bidirectional"))
    )
    (net (code "67") (name "UART2_RX") (class "Default")
      (node (ref "R16") (pin "2") (pinfunction "2_2") (pintype "passive"))
      (node (ref "R29") (pin "2") (pinfunction "2_2") (pintype "passive"))
      (node (ref "U$1") (pin "D16") (pinfunction "IO16_D16") (pintype "bidirectional"))
    )
    (net (code "68") (name "UART2_TX") (class "Default")
      (node (ref "Q1") (pin "S") (pinfunction "S_S") (pintype "passive"))
      (node (ref "R22") (pin "1") (pinfunction "1_1") (pintype "passive"))
      (node (ref "U$1") (pin "D17") (pinfunction "IO17_D17") (pintype "bidirectional"))
    )
    (net (code "69") (name "unconnected-(U$3-PadAD0)") (class "Default")
      (node (ref "U$3") (pin "AD0") (pinfunction "AD0_AD0") (pintype "bidirectional"))
    )
    (net (code "70") (name "unconnected-(U$3-PadECL)") (class "Default")
      (node (ref "U$3") (pin "ECL") (pinfunction "ECL_ECL") (pintype "bidirectional"))
    )
    (net (code "71") (name "unconnected-(U$3-PadEDA)") (class "Default")
      (node (ref "U$3") (pin "EDA") (pinfunction "EDA_EDA") (pintype "bidirectional"))
    )
    (net (code "72") (name "unconnected-(U$3-PadINT)") (class "Default")
      (node (ref "U$3") (pin "INT") (pinfunction "INT_INT") (pintype "bidirectional"))
    )
    (net (code "73") (name "unconnected-(U$3-PadNCS)") (class "Default")
      (node (ref "U$3") (pin "NCS") (pinfunction "NCS_NCS") (pintype "bidirectional"))
    )
    (net (code "74") (name "unconnected-(U$6-IO2{slash}CTS1-PadIO2)") (class "Default")
      (node (ref "U$6") (pin "IO2") (pinfunction "IO2/CTS1_IO2") (pintype "bidirectional"))
    )
    (net (code "75") (name "unconnected-(U$6-IO3{slash}RTS1-PadIO3)") (class "Default")
      (node (ref "U$6") (pin "IO3") (pinfunction "IO3/RTS1_IO3") (pintype "bidirectional"))
    )
    (net (code "76") (name "unconnected-(U$6-IO4{slash}RX2-PadIO4)") (class "Default")
      (node (ref "U$6") (pin "IO4") (pinfunction "IO4/RX2_IO4") (pintype "bidirectional"))
    )
    (net (code "77") (name "unconnected-(U$6-IO5{slash}TX2-PadIO5)") (class "Default")
      (node (ref "U$6") (pin "IO5") (pinfunction "IO5/TX2_IO5") (pintype "bidirectional"))
    )
    (net (code "78") (name "unconnected-(U$6-IO6{slash}CTS2-PadIO6)") (class "Default")
      (node (ref "U$6") (pin "IO6") (pinfunction "IO6/CTS2_IO6") (pintype "bidirectional"))
    )
    (net (code "79") (name "unconnected-(U$6-IO7{slash}RTS2-PadIO7)") (class "Default")
      (node (ref "U$6") (pin "IO7") (pinfunction "IO7/RTS2_IO7") (pintype "bidirectional"))
    )
    (net (code "80") (name "unconnected-(U$6-IO19{slash}I2C2_SCL-PadIO19)") (class "Default")
      (node (ref "U$6") (pin "IO19") (pinfunction "IO19/I2C2_SCL_IO19") (pintype "bidirectional"))
    )
    (net (code "81") (name "unconnected-(U$6-IO20{slash}I2C2_SDA-PadIO20)") (class "Default")
      (node (ref "U$6") (pin "IO20") (pinfunction "IO20/I2C2_SDA_IO20") (pintype "bidirectional"))
    )
    (net (code "82") (name "unconnected-(U$6-PadADC0)") (class "Default")
      (node (ref "U$6") (pin "ADC0") (pinfunction "ADC0_ADC0") (pintype "bidirectional"))
    )
    (net (code "83") (name "unconnected-(U$6-PadADC1)") (class "Default")
      (node (ref "U$6") (pin "ADC1") (pinfunction "ADC1_ADC1") (pintype "bidirectional"))
    )
    (net (code "84") (name "unconnected-(U$6-PadHST_RX)") (class "Default")
      (node (ref "U$6") (pin "HST_RX") (pinfunction "HST_RX_HST_RX") (pintype "bidirectional"))
    )
    (net (code "85") (name "unconnected-(U$6-PadHST_TX)") (class "Default")
      (node (ref "U$6") (pin "HST_TX") (pinfunction "HST_TX_HST_TX") (pintype "bidirectional"))
    )
    (net (code "86") (name "unconnected-(U$6-PadIO14)") (class "Default")
      (node (ref "U$6") (pin "IO14") (pinfunction "IO14_IO14") (pintype "bidirectional"))
    )
    (net (code "87") (name "unconnected-(U$6-PadIO15)") (class "Default")
      (node (ref "U$6") (pin "IO15") (pinfunction "IO15_IO15") (pintype "bidirectional"))
    )
    (net (code "88") (name "unconnected-(U$6-PadIO16)") (class "Default")
      (node (ref "U$6") (pin "IO16") (pinfunction "IO16_IO16") (pintype "bidirectional"))
    )
    (net (code "89") (name "unconnected-(U$6-PadIO17)") (class "Default")
      (node (ref "U$6") (pin "IO17") (pinfunction "IO17_IO17") (pintype "bidirectional"))
    )
    (net (code "90") (name "unconnected-(U$6-PadIO18)") (class "Default")
      (node (ref "U$6") (pin "IO18") (pinfunction "IO18_IO18") (pintype "bidirectional"))
    )
    (net (code "91") (name "unconnected-(U$6-PadIO25)") (class "Default")
      (node (ref "U$6") (pin "IO25") (pinfunction "IO25_IO25") (pintype "bidirectional"))
    )
    (net (code "92") (name "unconnected-(U$6-PadIO26)") (class "Default")
      (node (ref "U$6") (pin "IO26") (pinfunction "IO26_IO26") (pintype "bidirectional"))
    )
    (net (code "93") (name "unconnected-(U$6-PadIO29)") (class "Default")
      (node (ref "U$6") (pin "IO29") (pinfunction "IO29_IO29") (pintype "bidirectional"))
    )
    (net (code "94") (name "unconnected-(U$6-PadIO30)") (class "Default")
      (node (ref "U$6") (pin "IO30") (pinfunction "IO30_IO30") (pintype "bidirectional"))
    )
    (net (code "95") (name "unconnected-(U$6-PadPWR_KEY)") (class "Default")
      (node (ref "U$6") (pin "PWR_KEY") (pinfunction "PWR_KEY_PWR_KEY") (pintype "bidirectional"))
    )
    (net (code "96") (name "unconnected-(U$6-PadVBAT)") (class "Default")
      (node (ref "U$6") (pin "VBAT") (pinfunction "VBAT_VBAT") (pintype "bidirectional"))
    )
    (net (code "97") (name "unconnected-(U$6-PadVIO)") (class "Default")
      (node (ref "U$6") (pin "VIO") (pinfunction "VIO_VIO") (pintype "bidirectional"))
    )
  )
)
